# Eagle_Teensy3_6_TAF_BoardV2_2.net
KiCad netlist of a schematic drawn in EAGLE
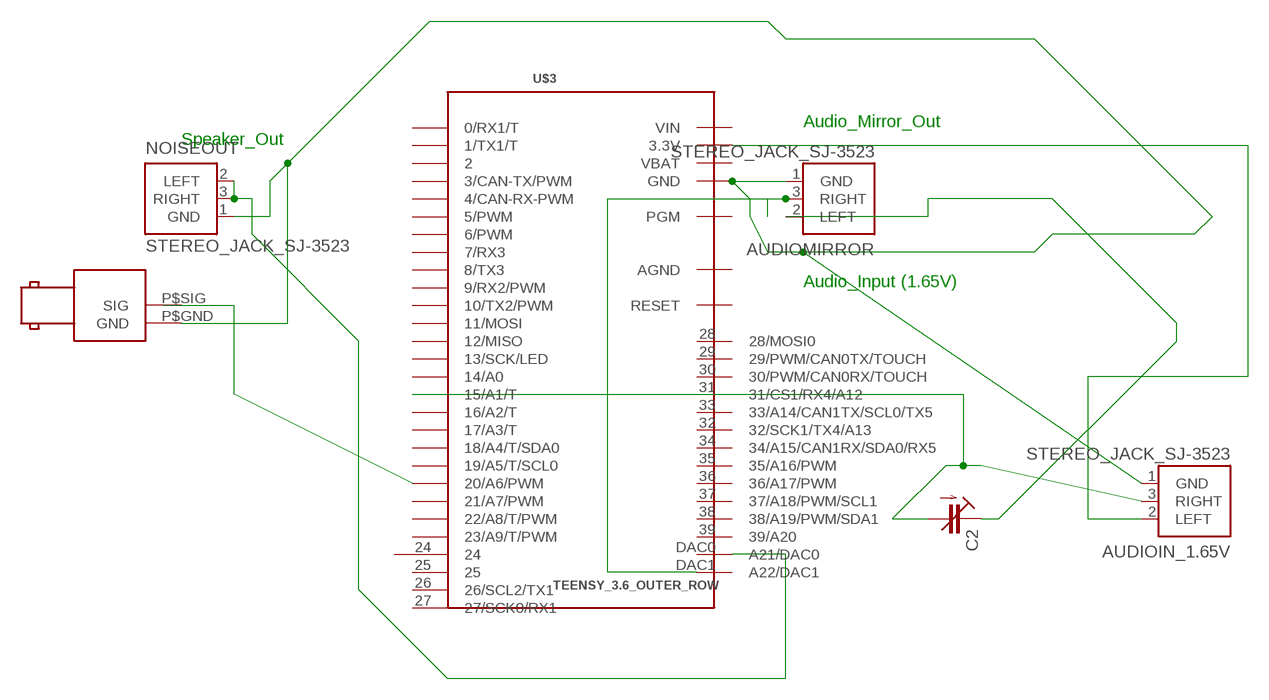
[diagram p0: schematic, sheet 1]

(export (version "E")
  (design (tool "Eeschema 10.0.6"))
  (components
    (comp (ref "AUDIOIN_1.65V")
      (value "STEREO_JACK_SJ-3523")
      (footprint "eagle-import:SJ-3523")
      (libsource (lib "eagle-import") (part "STEREO_JACK_SJ-3523"))
    )
    (comp (ref "AUDIOMIRROR")
      (value "STEREO_JACK_SJ-3523")
      (footprint "eagle-import:SJ-3523")
      (libsource (lib "eagle-import") (part "STEREO_JACK_SJ-3523"))
    )
    (comp (ref "C2")
      (value "C-TRIMM3008")
      (footprint "eagle-import:3008")
      (libsource (lib "eagle-import") (part "C-TRIMM3008"))
    )
    (comp (ref "NOISEOUT")
      (value "STEREO_JACK_SJ-3523")
      (footprint "eagle-import:SJ-3523")
      (libsource (lib "eagle-import") (part "STEREO_JACK_SJ-3523"))
    )
    (comp (ref "TTL")
      (value "BNC_RIGHT_ANGLE")
      (footprint "eagle-import:BNC_RIGHT_ANGLE")
      (libsource (lib "eagle-import") (part "BNC_RIGHT_ANGLE"))
    )
    (comp (ref "U$3")
      (value "TEENSY_3.6_OUTER_ROW")
      (footprint "eagle-import:TEENSY3_6-OUTER_ROW")
      (libsource (lib "eagle-import") (part "TEENSY_3.6_OUTER_ROW"))
    )
  )
  (nets
    (net (code "1") (name "/AGND") (class "Default")
      (node (ref "U$3") (pin "AGND") (pinfunction "AGND_AGND") (pintype "power_in"))
    )
    (net (code "2") (name "/VBAT") (class "Default")
      (node (ref "U$3") (pin "VBAT") (pinfunction "VBAT_VBAT") (pintype "power_in"))
    )
    (net (code "3") (name "/VIN") (class "Default")
      (node (ref "U$3") (pin "VIN") (pinfunction "VIN_VIN") (pintype "power_in"))
    )
    (net (code "4") (name "Net-(AUDIOIN_1.65V-GND)") (class "Default")
      (node (ref "AUDIOIN_1.65V") (pin "1") (pinfunction "GND_1") (pintype "power_in"))
      (node (ref "AUDIOMIRROR") (pin "1") (pinfunction "GND_1") (pintype "power_in"))
      (node (ref "NOISEOUT") (pin "1") (pinfunction "GND_1") (pintype "power_in"))
      (node (ref "TTL") (pin "P$GND") (pinfunction "GND_P$GND") (pintype "bidirectional"))
      (node (ref "U$3") (pin "3.3V2") (pinfunction "GND_3.3V2") (pintype "power_in"))
      (node (ref "U$3") (pin "GND") (pinfunction "GND_GND") (pintype "power_in"))
      (node (ref "U$3") (pin "GND1") (pinfunction "GND_GND1") (pintype "power_in"))
      (node (ref "U$3") (pin "GND2") (pinfunction "GND_GND2") (pintype "power_in"))
    )
    (net (code "5") (name "Net-(AUDIOIN_1.65V-LEFT)") (class "Default")
      (node (ref "AUDIOIN_1.65V") (pin "2") (pinfunction "LEFT_2") (pintype "output"))
      (node (ref "U$3") (pin "3.3V") (pinfunction "3.3V_3.3V") (pintype "power_in"))
      (node (ref "U$3") (pin "3.3V1") (pinfunction "3.3V_3.3V1") (pintype "power_in"))
    )
    (net (code "6") (name "Net-(AUDIOIN_1.65V-RIGHT)") (class "Default")
      (node (ref "AUDIOIN_1.65V") (pin "3") (pinfunction "RIGHT_3") (pintype "output"))
      (node (ref "C2") (pin "-") (pinfunction "A_-") (pintype "passive"))
      (node (ref "U$3") (pin "15/A1") (pinfunction "15/A1/T_15/A1") (pintype "bidirectional"))
    )
    (net (code "7") (name "Net-(AUDIOMIRROR-LEFT)") (class "Default")
      (node (ref "AUDIOMIRROR") (pin "2") (pinfunction "LEFT_2") (pintype "output"))
      (node (ref "C2") (pin "+") (pinfunction "E_+") (pintype "passive"))
    )
    (net (code "8") (name "Net-(AUDIOMIRROR-RIGHT)") (class "Default")
      (node (ref "AUDIOMIRROR") (pin "3") (pinfunction "RIGHT_3") (pintype "output"))
      (node (ref "U$3") (pin "DAC1") (pinfunction "A22/DAC1_DAC1") (pintype "bidirectional"))
    )
    (net (code "9") (name "Net-(NOISEOUT-LEFT)") (class "Default")
      (node (ref "NOISEOUT") (pin "2") (pinfunction "LEFT_2") (pintype "output"))
      (node (ref "NOISEOUT") (pin "3") (pinfunction "RIGHT_3") (pintype "output"))
    )
    (net (code "10") (name "unconnected-(TTL-SIG-PadP$SIG)") (class "Default")
      (node (ref "TTL") (pin "P$SIG") (pinfunction "SIG_P$SIG") (pintype "bidirectional"))
    )
    (net (code "11") (name "unconnected-(U$3-0{slash}RX1{slash}T-Pad0)") (class "Default")
      (node (ref "U$3") (pin "0") (pinfunction "0/RX1/T_0") (pintype "bidirectional"))
    )
    (net (code "12") (name "unconnected-(U$3-1{slash}TX1{slash}T-Pad1)") (class "Default")
      (node (ref "U$3") (pin "1") (pinfunction "1/TX1/T_1") (pintype "bidirectional"))
    )
    (net (code "13") (name "unconnected-(U$3-3{slash}CAN-TX{slash}PWM-Pad3)") (class "Default")
      (node (ref "U$3") (pin "3") (pinfunction "3/CAN-TX/PWM_3") (pintype "bidirectional"))
    )
    (net (code "14") (name "unconnected-(U$3-4{slash}CAN-RX-PWM-Pad4)") (class "Default")
      (node (ref "U$3") (pin "4") (pinfunction "4/CAN-RX-PWM_4") (pintype "bidirectional"))
    )
    (net (code "15") (name "unconnected-(U$3-5{slash}PWM-Pad5)") (class "Default")
      (node (ref "U$3") (pin "5") (pinfunction "5/PWM_5") (pintype "bidirectional"))
    )
    (net (code "16") (name "unconnected-(U$3-6{slash}PWM-Pad6)") (class "Default")
      (node (ref "U$3") (pin "6") (pinfunction "6/PWM_6") (pintype "bidirectional"))
    )
    (net (code "17") (name "unconnected-(U$3-7{slash}RX3-Pad7)") (class "Default")
      (node (ref "U$3") (pin "7") (pinfunction "7/RX3_7") (pintype "bidirectional"))
    )
    (net (code "18") (name "unconnected-(U$3-8{slash}TX3-Pad8)") (class "Default")
      (node (ref "U$3") (pin "8") (pinfunction "8/TX3_8") (pintype "bidirectional"))
    )
    (net (code "19") (name "unconnected-(U$3-9{slash}RX2{slash}PWM-Pad9)") (class "Default")
      (node (ref "U$3") (pin "9") (pinfunction "9/RX2/PWM_9") (pintype "bidirectional"))
    )
    (net (code "20") (name "unconnected-(U$3-10{slash}TX2{slash}PWM-Pad10)") (class "Default")
      (node (ref "U$3") (pin "10") (pinfunction "10/TX2/PWM_10") (pintype "bidirectional"))
    )
    (net (code "21") (name "unconnected-(U$3-11{slash}MOSI-Pad11)") (class "Default")
      (node (ref "U$3") (pin "11") (pinfunction "11/MOSI_11") (pintype "bidirectional"))
    )
    (net (code "22") (name "unconnected-(U$3-12{slash}MISO-Pad12)") (class "Default")
      (node (ref "U$3") (pin "12") (pinfunction "12/MISO_12") (pintype "bidirectional"))
    )
    (net (code "23") (name "unconnected-(U$3-13{slash}SCK{slash}LED-Pad13)") (class "Default")
      (node (ref "U$3") (pin "13") (pinfunction "13/SCK/LED_13") (pintype "bidirectional"))
    )
    (net (code "24") (name "unconnected-(U$3-16{slash}A2{slash}T-Pad16{slash}A2)") (class "Default")
      (node (ref "U$3") (pin "16/A2") (pinfunction "16/A2/T_16/A2") (pintype "bidirectional"))
    )
    (net (code "25") (name "unconnected-(U$3-17{slash}A3{slash}T-Pad17{slash}A3)") (class "Default")
      (node (ref "U$3") (pin "17/A3") (pinfunction "17/A3/T_17/A3") (pintype "bidirectional"))
    )
    (net (code "26") (name "unconnected-(U$3-18{slash}A4{slash}T{slash}SDA0-Pad18{slash}A4)") (class "Default")
      (node (ref "U$3") (pin "18/A4") (pinfunction "18/A4/T/SDA0_18/A4") (pintype "bidirectional"))
    )
    (net (code "27") (name "unconnected-(U$3-19{slash}A5{slash}T{slash}SCL0-Pad19{slash}A5)") (class "Default")
      (node (ref "U$3") (pin "19/A5") (pinfunction "19/A5/T/SCL0_19/A5") (pintype "bidirectional"))
    )
    (net (code "28") (name "unconnected-(U$3-20{slash}A6{slash}PWM-Pad20{slash}A6)") (class "Default")
      (node (ref "U$3") (pin "20/A6") (pinfunction "20/A6/PWM_20/A6") (pintype "bidirectional"))
    )
    (net (code "29") (name "unconnected-(U$3-21{slash}A7{slash}PWM-Pad21{slash}A7)") (class "Default")
      (node (ref "U$3") (pin "21/A7") (pinfunction "21/A7/PWM_21/A7") (pintype "bidirectional"))
    )
    (net (code "30") (name "unconnected-(U$3-22{slash}A8{slash}T{slash}PWM-Pad22{slash}A8)") (class "Default")
      (node (ref "U$3") (pin "22/A8") (pinfunction "22/A8/T/PWM_22/A8") (pintype "bidirectional"))
    )
    (net (code "31") (name "unconnected-(U$3-23{slash}A9{slash}T{slash}PWM-Pad23{slash}A9)") (class "Default")
      (node (ref "U$3") (pin "23/A9") (pinfunction "23/A9/T/PWM_23/A9") (pintype "bidirectional"))
    )
    (net (code "32") (name "unconnected-(U$3-26{slash}SCL2{slash}TX1-Pad26)") (class "Default")
      (node (ref "U$3") (pin "26") (pinfunction "26/SCL2/TX1_26") (pintype "bidirectional"))
    )
    (net (code "33") (name "unconnected-(U$3-27{slash}SCK0{slash}RX1-Pad27)") (class "Default")
      (node (ref "U$3") (pin "27") (pinfunction "27/SCK0/RX1_27") (pintype "bidirectional"))
    )
    (net (code "34") (name "unconnected-(U$3-28{slash}MOSI0-Pad28)") (class "Default")
      (node (ref "U$3") (pin "28") (pinfunction "28/MOSI0_28") (pintype "bidirectional"))
    )
    (net (code "35") (name "unconnected-(U$3-29{slash}PWM{slash}CAN0TX{slash}TOUCH-Pad29)") (class "Default")
      (node (ref "U$3") (pin "29") (pinfunction "29/PWM/CAN0TX/TOUCH_29") (pintype "bidirectional"))
    )
    (net (code "36") (name "unconnected-(U$3-30{slash}PWM{slash}CAN0RX{slash}TOUCH-Pad30)") (class "Default")
      (node (ref "U$3") (pin "30") (pinfunction "30/PWM/CAN0RX/TOUCH_30") (pintype "bidirectional"))
    )
    (net (code "37") (name "unconnected-(U$3-31{slash}CS1{slash}RX4{slash}A12-Pad31)") (class "Default")
      (node (ref "U$3") (pin "31") (pinfunction "31/CS1/RX4/A12_31") (pintype "bidirectional"))
    )
    (net (code "38") (name "unconnected-(U$3-32{slash}SCK1{slash}TX4{slash}A13-Pad32)") (class "Default")
      (node (ref "U$3") (pin "32") (pinfunction "32/SCK1/TX4/A13_32") (pintype "bidirectional"))
    )
    (net (code "39") (name "unconnected-(U$3-33{slash}A14{slash}CAN1TX{slash}SCL0{slash}TX5-Pad33)") (class "Default")
      (node (ref "U$3") (pin "33") (pinfunction "33/A14/CAN1TX/SCL0/TX5_33") (pintype "bidirectional"))
    )
    (net (code "40") (name "unconnected-(U$3-34{slash}A15{slash}CAN1RX{slash}SDA0{slash}RX5-Pad34)") (class "Default")
      (node (ref "U$3") (pin "34") (pinfunction "34/A15/CAN1RX/SDA0/RX5_34") (pintype "bidirectional"))
    )
    (net (code "41") (name "unconnected-(U$3-35{slash}A16{slash}PWM-Pad35)") (class "Default")
      (node (ref "U$3") (pin "35") (pinfunction "35/A16/PWM_35") (pintype "bidirectional"))
    )
    (net (code "42") (name "unconnected-(U$3-36{slash}A17{slash}PWM-Pad36)") (class "Default")
      (node (ref "U$3") (pin "36") (pinfunction "36/A17/PWM_36") (pintype "bidirectional"))
    )
    (net (code "43") (name "unconnected-(U$3-37{slash}A18{slash}PWM{slash}SCL1-Pad37)") (class "Default")
      (node (ref "U$3") (pin "37") (pinfunction "37/A18/PWM/SCL1_37") (pintype "bidirectional"))
    )
    (net (code "44") (name "unconnected-(U$3-38{slash}A19{slash}PWM{slash}SDA1-Pad38)") (class "Default")
      (node (ref "U$3") (pin "38") (pinfunction "38/A19/PWM/SDA1_38") (pintype "bidirectional"))
    )
    (net (code "45") (name "unconnected-(U$3-39{slash}A20-Pad39)") (class "Default")
      (node (ref "U$3") (pin "39") (pinfunction "39/A20_39") (pintype "bidirectional"))
    )
    (net (code "46") (name "unconnected-(U$3-A21{slash}DAC0-PadDAC0)") (class "Default")
      (node (ref "U$3") (pin "DAC0") (pinfunction "A21/DAC0_DAC0") (pintype "bidirectional"))
    )
    (net (code "47") (name "unconnected-(U$3-Pad2)") (class "Default")
      (node (ref "U$3") (pin "2") (pinfunction "2_2") (pintype "bidirectional"))
    )
    (net (code "48") (name "unconnected-(U$3-Pad14{slash}A0)") (class "Default")
      (node (ref "U$3") (pin "14/A0") (pinfunction "14/A0_14/A0") (pintype "bidirectional"))
    )
    (net (code "49") (name "unconnected-(U$3-Pad24)") (class "Default")
      (node (ref "U$3") (pin "24") (pinfunction "24_24") (pintype "bidirectional"))
    )
    (net (code "50") (name "unconnected-(U$3-Pad25)") (class "Default")
      (node (ref "U$3") (pin "25") (pinfunction "25_25") (pintype "bidirectional"))
    )
    (net (code "51") (name "unconnected-(U$3-PadPGM)") (class "Default")
      (node (ref "U$3") (pin "PGM") (pinfunction "PGM_PGM") (pintype "bidirectional"))
    )
    (net (code "52") (name "unconnected-(U$3-PadRESET)") (class "Default")
      (node (ref "U$3") (pin "RESET") (pinfunction "RESET_RESET") (pintype "bidirectional"))
    )
  )
)
